# rgb_chronos.net
KiCad netlist of a schematic drawn in EAGLE
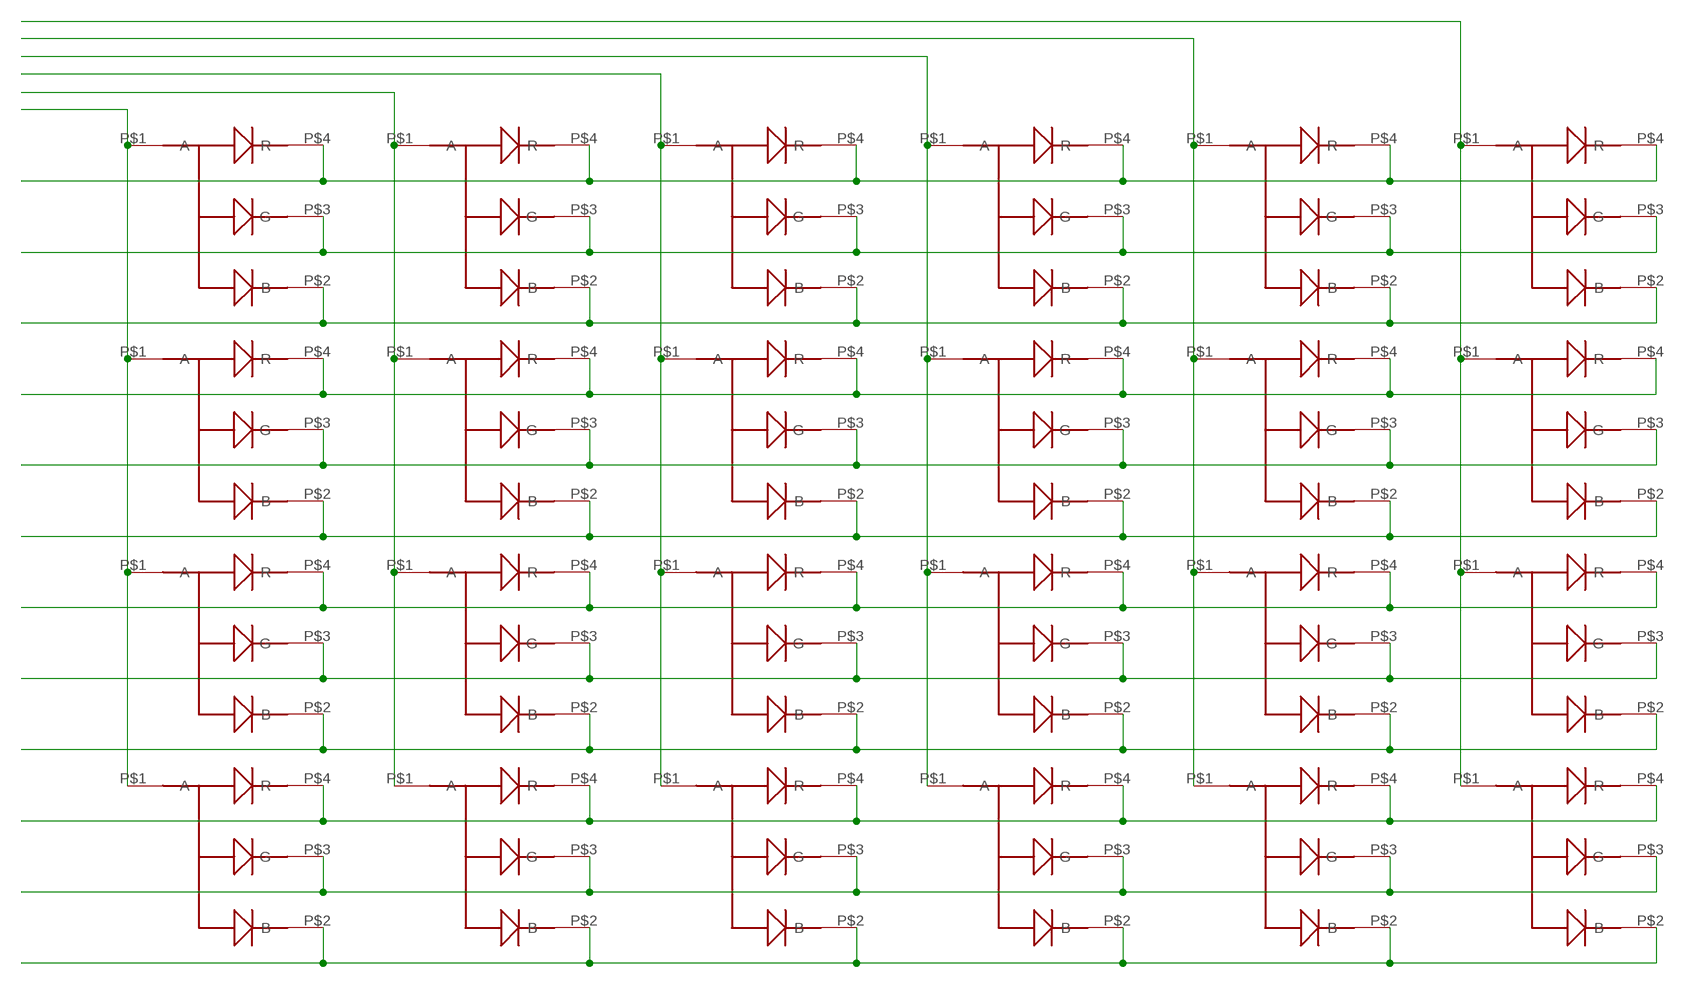
[diagram p0: schematic, sheet 1]

(export (version "E")
  (design (tool "Eeschema 10.0.6"))
  (components
    (comp (ref "U$1")
      (value "ASMB-MTB0-0A3A2")
      (footprint "eagle-import:PLCC4-LED")
      (libsource (lib "eagle-import") (part "LED3_ARGB"))
    )
    (comp (ref "U$2")
      (value "ASMB-MTB0-0A3A2")
      (footprint "eagle-import:PLCC4-LED")
      (libsource (lib "eagle-import") (part "LED3_ARGB"))
    )
    (comp (ref "U$3")
      (value "ASMB-MTB0-0A3A2")
      (footprint "eagle-import:PLCC4-LED")
      (libsource (lib "eagle-import") (part "LED3_ARGB"))
    )
    (comp (ref "U$4")
      (value "ASMB-MTB0-0A3A2")
      (footprint "eagle-import:PLCC4-LED")
      (libsource (lib "eagle-import") (part "LED3_ARGB"))
    )
    (comp (ref "U$5")
      (value "ASMB-MTB0-0A3A2")
      (footprint "eagle-import:PLCC4-LED")
      (libsource (lib "eagle-import") (part "LED3_ARGB"))
    )
    (comp (ref "U$6")
      (value "ASMB-MTB0-0A3A2")
      (footprint "eagle-import:PLCC4-LED")
      (libsource (lib "eagle-import") (part "LED3_ARGB"))
    )
    (comp (ref "U$7")
      (value "ASMB-MTB0-0A3A2")
      (footprint "eagle-import:PLCC4-LED")
      (libsource (lib "eagle-import") (part "LED3_ARGB"))
    )
    (comp (ref "U$8")
      (value "ASMB-MTB0-0A3A2")
      (footprint "eagle-import:PLCC4-LED")
      (libsource (lib "eagle-import") (part "LED3_ARGB"))
    )
    (comp (ref "U$9")
      (value "ASMB-MTB0-0A3A2")
      (footprint "eagle-import:PLCC4-LED")
      (libsource (lib "eagle-import") (part "LED3_ARGB"))
    )
    (comp (ref "U$10")
      (value "ASMB-MTB0-0A3A2")
      (footprint "eagle-import:PLCC4-LED")
      (libsource (lib "eagle-import") (part "LED3_ARGB"))
    )
    (comp (ref "U$11")
      (value "ASMB-MTB0-0A3A2")
      (footprint "eagle-import:PLCC4-LED")
      (libsource (lib "eagle-import") (part "LED3_ARGB"))
    )
    (comp (ref "U$12")
      (value "ASMB-MTB0-0A3A2")
      (footprint "eagle-import:PLCC4-LED")
      (libsource (lib "eagle-import") (part "LED3_ARGB"))
    )
    (comp (ref "U$13")
      (value "ASMB-MTB0-0A3A2")
      (footprint "eagle-import:PLCC4-LED")
      (libsource (lib "eagle-import") (part "LED3_ARGB"))
    )
    (comp (ref "U$14")
      (value "ASMB-MTB0-0A3A2")
      (footprint "eagle-import:PLCC4-LED")
      (libsource (lib "eagle-import") (part "LED3_ARGB"))
    )
    (comp (ref "U$15")
      (value "ASMB-MTB0-0A3A2")
      (footprint "eagle-import:PLCC4-LED")
      (libsource (lib "eagle-import") (part "LED3_ARGB"))
    )
    (comp (ref "U$16")
      (value "ASMB-MTB0-0A3A2")
      (footprint "eagle-import:PLCC4-LED")
      (libsource (lib "eagle-import") (part "LED3_ARGB"))
    )
    (comp (ref "U$17")
      (value "ASMB-MTB0-0A3A2")
      (footprint "eagle-import:PLCC4-LED")
      (libsource (lib "eagle-import") (part "LED3_ARGB"))
    )
    (comp (ref "U$18")
      (value "ASMB-MTB0-0A3A2")
      (footprint "eagle-import:PLCC4-LED")
      (libsource (lib "eagle-import") (part "LED3_ARGB"))
    )
    (comp (ref "U$19")
      (value "ASMB-MTB0-0A3A2")
      (footprint "eagle-import:PLCC4-LED")
      (libsource (lib "eagle-import") (part "LED3_ARGB"))
    )
    (comp (ref "U$20")
      (value "ASMB-MTB0-0A3A2")
      (footprint "eagle-import:PLCC4-LED")
      (libsource (lib "eagle-import") (part "LED3_ARGB"))
    )
    (comp (ref "U$21")
      (value "ASMB-MTB0-0A3A2")
      (footprint "eagle-import:PLCC4-LED")
      (libsource (lib "eagle-import") (part "LED3_ARGB"))
    )
    (comp (ref "U$22")
      (value "ASMB-MTB0-0A3A2")
      (footprint "eagle-import:PLCC4-LED")
      (libsource (lib "eagle-import") (part "LED3_ARGB"))
    )
    (comp (ref "U$23")
      (value "ASMB-MTB0-0A3A2")
      (footprint "eagle-import:PLCC4-LED")
      (libsource (lib "eagle-import") (part "LED3_ARGB"))
    )
    (comp (ref "U$24")
      (value "ASMB-MTB0-0A3A2")
      (footprint "eagle-import:PLCC4-LED")
      (libsource (lib "eagle-import") (part "LED3_ARGB"))
    )
  )
  (nets
    (net (code "1") (name "Net-(U$1-A)") (class "Default")
      (node (ref "U$1") (pin "P$1") (pinfunction "A_P$1") (pintype "bidirectional"))
      (node (ref "U$2") (pin "P$1") (pinfunction "A_P$1") (pintype "bidirectional"))
      (node (ref "U$3") (pin "P$1") (pinfunction "A_P$1") (pintype "bidirectional"))
      (node (ref "U$4") (pin "P$1") (pinfunction "A_P$1") (pintype "bidirectional"))
    )
    (net (code "2") (name "Net-(U$1-B)") (class "Default")
      (node (ref "U$1") (pin "P$2") (pinfunction "B_P$2") (pintype "bidirectional"))
      (node (ref "U$13") (pin "P$2") (pinfunction "B_P$2") (pintype "bidirectional"))
      (node (ref "U$17") (pin "P$2") (pinfunction "B_P$2") (pintype "bidirectional"))
      (node (ref "U$21") (pin "P$2") (pinfunction "B_P$2") (pintype "bidirectional"))
      (node (ref "U$5") (pin "P$2") (pinfunction "B_P$2") (pintype "bidirectional"))
      (node (ref "U$9") (pin "P$2") (pinfunction "B_P$2") (pintype "bidirectional"))
    )
    (net (code "3") (name "Net-(U$1-G)") (class "Default")
      (node (ref "U$1") (pin "P$3") (pinfunction "G_P$3") (pintype "bidirectional"))
      (node (ref "U$13") (pin "P$3") (pinfunction "G_P$3") (pintype "bidirectional"))
      (node (ref "U$17") (pin "P$3") (pinfunction "G_P$3") (pintype "bidirectional"))
      (node (ref "U$21") (pin "P$3") (pinfunction "G_P$3") (pintype "bidirectional"))
      (node (ref "U$5") (pin "P$3") (pinfunction "G_P$3") (pintype "bidirectional"))
      (node (ref "U$9") (pin "P$3") (pinfunction "G_P$3") (pintype "bidirectional"))
    )
    (net (code "4") (name "Net-(U$1-R)") (class "Default")
      (node (ref "U$1") (pin "P$4") (pinfunction "R_P$4") (pintype "bidirectional"))
      (node (ref "U$13") (pin "P$4") (pinfunction "R_P$4") (pintype "bidirectional"))
      (node (ref "U$17") (pin "P$4") (pinfunction "R_P$4") (pintype "bidirectional"))
      (node (ref "U$21") (pin "P$4") (pinfunction "R_P$4") (pintype "bidirectional"))
      (node (ref "U$5") (pin "P$4") (pinfunction "R_P$4") (pintype "bidirectional"))
      (node (ref "U$9") (pin "P$4") (pinfunction "R_P$4") (pintype "bidirectional"))
    )
    (net (code "5") (name "Net-(U$5-A)") (class "Default")
      (node (ref "U$5") (pin "P$1") (pinfunction "A_P$1") (pintype "bidirectional"))
      (node (ref "U$6") (pin "P$1") (pinfunction "A_P$1") (pintype "bidirectional"))
      (node (ref "U$7") (pin "P$1") (pinfunction "A_P$1") (pintype "bidirectional"))
      (node (ref "U$8") (pin "P$1") (pinfunction "A_P$1") (pintype "bidirectional"))
    )
    (net (code "6") (name "Net-(U$10-A)") (class "Default")
      (node (ref "U$10") (pin "P$1") (pinfunction "A_P$1") (pintype "bidirectional"))
      (node (ref "U$11") (pin "P$1") (pinfunction "A_P$1") (pintype "bidirectional"))
      (node (ref "U$12") (pin "P$1") (pinfunction "A_P$1") (pintype "bidirectional"))
      (node (ref "U$9") (pin "P$1") (pinfunction "A_P$1") (pintype "bidirectional"))
    )
    (net (code "7") (name "Net-(U$10-B)") (class "Default")
      (node (ref "U$10") (pin "P$2") (pinfunction "B_P$2") (pintype "bidirectional"))
      (node (ref "U$14") (pin "P$2") (pinfunction "B_P$2") (pintype "bidirectional"))
      (node (ref "U$18") (pin "P$2") (pinfunction "B_P$2") (pintype "bidirectional"))
      (node (ref "U$2") (pin "P$2") (pinfunction "B_P$2") (pintype "bidirectional"))
      (node (ref "U$22") (pin "P$2") (pinfunction "B_P$2") (pintype "bidirectional"))
      (node (ref "U$6") (pin "P$2") (pinfunction "B_P$2") (pintype "bidirectional"))
    )
    (net (code "8") (name "Net-(U$10-G)") (class "Default")
      (node (ref "U$10") (pin "P$3") (pinfunction "G_P$3") (pintype "bidirectional"))
      (node (ref "U$14") (pin "P$3") (pinfunction "G_P$3") (pintype "bidirectional"))
      (node (ref "U$18") (pin "P$3") (pinfunction "G_P$3") (pintype "bidirectional"))
      (node (ref "U$2") (pin "P$3") (pinfunction "G_P$3") (pintype "bidirectional"))
      (node (ref "U$22") (pin "P$3") (pinfunction "G_P$3") (pintype "bidirectional"))
      (node (ref "U$6") (pin "P$3") (pinfunction "G_P$3") (pintype "bidirectional"))
    )
    (net (code "9") (name "Net-(U$10-R)") (class "Default")
      (node (ref "U$10") (pin "P$4") (pinfunction "R_P$4") (pintype "bidirectional"))
      (node (ref "U$14") (pin "P$4") (pinfunction "R_P$4") (pintype "bidirectional"))
      (node (ref "U$18") (pin "P$4") (pinfunction "R_P$4") (pintype "bidirectional"))
      (node (ref "U$2") (pin "P$4") (pinfunction "R_P$4") (pintype "bidirectional"))
      (node (ref "U$22") (pin "P$4") (pinfunction "R_P$4") (pintype "bidirectional"))
      (node (ref "U$6") (pin "P$4") (pinfunction "R_P$4") (pintype "bidirectional"))
    )
    (net (code "10") (name "Net-(U$11-B)") (class "Default")
      (node (ref "U$11") (pin "P$2") (pinfunction "B_P$2") (pintype "bidirectional"))
      (node (ref "U$15") (pin "P$2") (pinfunction "B_P$2") (pintype "bidirectional"))
      (node (ref "U$19") (pin "P$2") (pinfunction "B_P$2") (pintype "bidirectional"))
      (node (ref "U$23") (pin "P$2") (pinfunction "B_P$2") (pintype "bidirectional"))
      (node (ref "U$3") (pin "P$2") (pinfunction "B_P$2") (pintype "bidirectional"))
      (node (ref "U$7") (pin "P$2") (pinfunction "B_P$2") (pintype "bidirectional"))
    )
    (net (code "11") (name "Net-(U$11-G)") (class "Default")
      (node (ref "U$11") (pin "P$3") (pinfunction "G_P$3") (pintype "bidirectional"))
      (node (ref "U$15") (pin "P$3") (pinfunction "G_P$3") (pintype "bidirectional"))
      (node (ref "U$19") (pin "P$3") (pinfunction "G_P$3") (pintype "bidirectional"))
      (node (ref "U$23") (pin "P$3") (pinfunction "G_P$3") (pintype "bidirectional"))
      (node (ref "U$3") (pin "P$3") (pinfunction "G_P$3") (pintype "bidirectional"))
      (node (ref "U$7") (pin "P$3") (pinfunction "G_P$3") (pintype "bidirectional"))
    )
    (net (code "12") (name "Net-(U$11-R)") (class "Default")
      (node (ref "U$11") (pin "P$4") (pinfunction "R_P$4") (pintype "bidirectional"))
      (node (ref "U$15") (pin "P$4") (pinfunction "R_P$4") (pintype "bidirectional"))
      (node (ref "U$19") (pin "P$4") (pinfunction "R_P$4") (pintype "bidirectional"))
      (node (ref "U$23") (pin "P$4") (pinfunction "R_P$4") (pintype "bidirectional"))
      (node (ref "U$3") (pin "P$4") (pinfunction "R_P$4") (pintype "bidirectional"))
      (node (ref "U$7") (pin "P$4") (pinfunction "R_P$4") (pintype "bidirectional"))
    )
    (net (code "13") (name "Net-(U$12-B)") (class "Default")
      (node (ref "U$12") (pin "P$2") (pinfunction "B_P$2") (pintype "bidirectional"))
      (node (ref "U$16") (pin "P$2") (pinfunction "B_P$2") (pintype "bidirectional"))
      (node (ref "U$20") (pin "P$2") (pinfunction "B_P$2") (pintype "bidirectional"))
      (node (ref "U$24") (pin "P$2") (pinfunction "B_P$2") (pintype "bidirectional"))
      (node (ref "U$4") (pin "P$2") (pinfunction "B_P$2") (pintype "bidirectional"))
      (node (ref "U$8") (pin "P$2") (pinfunction "B_P$2") (pintype "bidirectional"))
    )
    (net (code "14") (name "Net-(U$12-G)") (class "Default")
      (node (ref "U$12") (pin "P$3") (pinfunction "G_P$3") (pintype "bidirectional"))
      (node (ref "U$16") (pin "P$3") (pinfunction "G_P$3") (pintype "bidirectional"))
      (node (ref "U$20") (pin "P$3") (pinfunction "G_P$3") (pintype "bidirectional"))
      (node (ref "U$24") (pin "P$3") (pinfunction "G_P$3") (pintype "bidirectional"))
      (node (ref "U$4") (pin "P$3") (pinfunction "G_P$3") (pintype "bidirectional"))
      (node (ref "U$8") (pin "P$3") (pinfunction "G_P$3") (pintype "bidirectional"))
    )
    (net (code "15") (name "Net-(U$12-R)") (class "Default")
      (node (ref "U$12") (pin "P$4") (pinfunction "R_P$4") (pintype "bidirectional"))
      (node (ref "U$16") (pin "P$4") (pinfunction "R_P$4") (pintype "bidirectional"))
      (node (ref "U$20") (pin "P$4") (pinfunction "R_P$4") (pintype "bidirectional"))
      (node (ref "U$24") (pin "P$4") (pinfunction "R_P$4") (pintype "bidirectional"))
      (node (ref "U$4") (pin "P$4") (pinfunction "R_P$4") (pintype "bidirectional"))
      (node (ref "U$8") (pin "P$4") (pinfunction "R_P$4") (pintype "bidirectional"))
    )
    (net (code "16") (name "Net-(U$13-A)") (class "Default")
      (node (ref "U$13") (pin "P$1") (pinfunction "A_P$1") (pintype "bidirectional"))
      (node (ref "U$14") (pin "P$1") (pinfunction "A_P$1") (pintype "bidirectional"))
      (node (ref "U$15") (pin "P$1") (pinfunction "A_P$1") (pintype "bidirectional"))
      (node (ref "U$16") (pin "P$1") (pinfunction "A_P$1") (pintype "bidirectional"))
    )
    (net (code "17") (name "Net-(U$17-A)") (class "Default")
      (node (ref "U$17") (pin "P$1") (pinfunction "A_P$1") (pintype "bidirectional"))
      (node (ref "U$18") (pin "P$1") (pinfunction "A_P$1") (pintype "bidirectional"))
      (node (ref "U$19") (pin "P$1") (pinfunction "A_P$1") (pintype "bidirectional"))
      (node (ref "U$20") (pin "P$1") (pinfunction "A_P$1") (pintype "bidirectional"))
    )
    (net (code "18") (name "Net-(U$21-A)") (class "Default")
      (node (ref "U$21") (pin "P$1") (pinfunction "A_P$1") (pintype "bidirectional"))
      (node (ref "U$22") (pin "P$1") (pinfunction "A_P$1") (pintype "bidirectional"))
      (node (ref "U$23") (pin "P$1") (pinfunction "A_P$1") (pintype "bidirectional"))
      (node (ref "U$24") (pin "P$1") (pinfunction "A_P$1") (pintype "bidirectional"))
    )
  )
)
